# OST.net
KiCad netlist of a schematic drawn in EAGLE
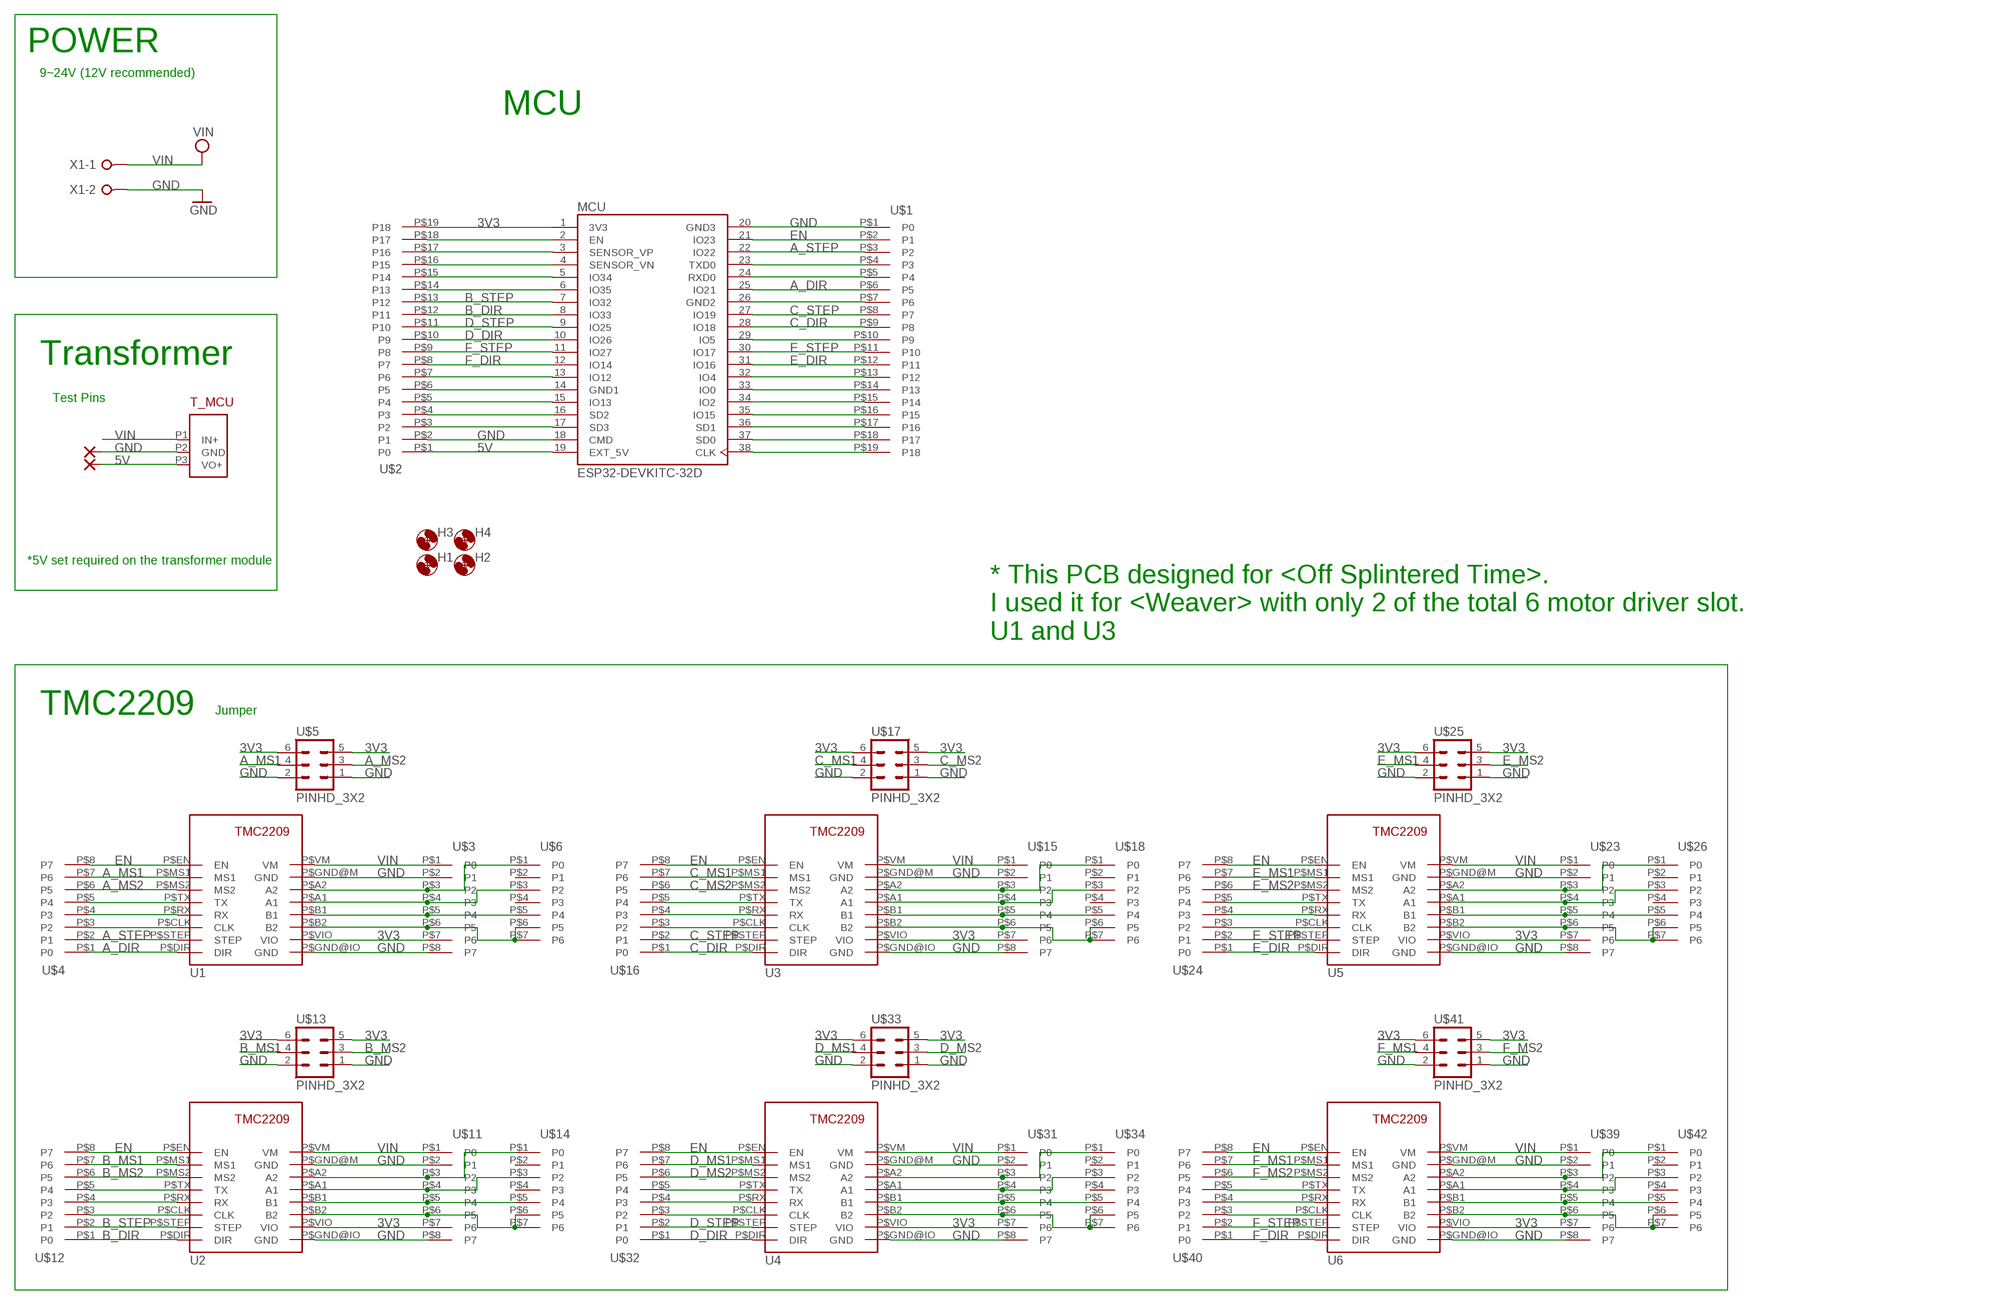
[diagram p0: schematic, sheet 1]

(export (version "E")
  (design (tool "Eeschema 10.0.6"))
  (components
    (comp (ref "H1")
      (value "MOUNT-HOLE3.2")
      (footprint "eagle-import:3,2")
      (libsource (lib "eagle-import") (part "MOUNT-HOLE3.2"))
    )
    (comp (ref "H2")
      (value "MOUNT-HOLE3.2")
      (footprint "eagle-import:3,2")
      (libsource (lib "eagle-import") (part "MOUNT-HOLE3.2"))
    )
    (comp (ref "H3")
      (value "MOUNT-HOLE3.2")
      (footprint "eagle-import:3,2")
      (libsource (lib "eagle-import") (part "MOUNT-HOLE3.2"))
    )
    (comp (ref "H4")
      (value "MOUNT-HOLE3.2")
      (footprint "eagle-import:3,2")
      (libsource (lib "eagle-import") (part "MOUNT-HOLE3.2"))
    )
    (comp (ref "MCU")
      (value "ESP32-DEVKITC-32D")
      (footprint "eagle-import:MODULE_ESP32-DEVKITC-32D")
      (fields (field (name "MANUFACTURER") "Espressif Systems"))
      (libsource (lib "eagle-import") (part "ESP32-DEVKITC-32D"))
    )
    (comp (ref "PAD16")
      (value "2,15/1,0")
      (footprint "eagle-import:2,15_1,0")
      (libsource (lib "eagle-import") (part "2,15/1,0"))
    )
    (comp (ref "PAD17")
      (value "2,15/1,0")
      (footprint "eagle-import:2,15_1,0")
      (libsource (lib "eagle-import") (part "2,15/1,0"))
    )
    (comp (ref "T_MCU")
      (value "VOL_ADJ")
      (footprint "eagle-import:FREEVOL")
      (libsource (lib "eagle-import") (part "VOL_ADJ"))
    )
    (comp (ref "U$1")
      (value "PINHD_1X19")
      (footprint "eagle-import:19")
      (libsource (lib "eagle-import") (part "PINHD_1X19"))
    )
    (comp (ref "U$2")
      (value "PINHD_1X19")
      (footprint "eagle-import:19")
      (libsource (lib "eagle-import") (part "PINHD_1X19"))
    )
    (comp (ref "U$3")
      (value "PINHD_1X8")
      (footprint "eagle-import:8")
      (libsource (lib "eagle-import") (part "PINHD_1X8"))
    )
    (comp (ref "U$4")
      (value "PINHD_1X8")
      (footprint "eagle-import:8")
      (libsource (lib "eagle-import") (part "PINHD_1X8"))
    )
    (comp (ref "U$5")
      (value "PINHD_3X2")
      (footprint "eagle-import:MA03-2")
      (libsource (lib "eagle-import") (part "PINHD_3X2"))
    )
    (comp (ref "U$6")
      (value "PINHD_1X7")
      (footprint "eagle-import:7")
      (libsource (lib "eagle-import") (part "PINHD_1X7"))
    )
    (comp (ref "U$11")
      (value "PINHD_1X8")
      (footprint "eagle-import:8")
      (libsource (lib "eagle-import") (part "PINHD_1X8"))
    )
    (comp (ref "U$12")
      (value "PINHD_1X8")
      (footprint "eagle-import:8")
      (libsource (lib "eagle-import") (part "PINHD_1X8"))
    )
    (comp (ref "U$13")
      (value "PINHD_3X2")
      (footprint "eagle-import:MA03-2")
      (libsource (lib "eagle-import") (part "PINHD_3X2"))
    )
    (comp (ref "U$14")
      (value "PINHD_1X7")
      (footprint "eagle-import:7")
      (libsource (lib "eagle-import") (part "PINHD_1X7"))
    )
    (comp (ref "U$15")
      (value "PINHD_1X8")
      (footprint "eagle-import:8")
      (libsource (lib "eagle-import") (part "PINHD_1X8"))
    )
    (comp (ref "U$16")
      (value "PINHD_1X8")
      (footprint "eagle-import:8")
      (libsource (lib "eagle-import") (part "PINHD_1X8"))
    )
    (comp (ref "U$17")
      (value "PINHD_3X2")
      (footprint "eagle-import:MA03-2")
      (libsource (lib "eagle-import") (part "PINHD_3X2"))
    )
    (comp (ref "U$18")
      (value "PINHD_1X7")
      (footprint "eagle-import:7")
      (libsource (lib "eagle-import") (part "PINHD_1X7"))
    )
    (comp (ref "U$23")
      (value "PINHD_1X8")
      (footprint "eagle-import:8")
      (libsource (lib "eagle-import") (part "PINHD_1X8"))
    )
    (comp (ref "U$24")
      (value "PINHD_1X8")
      (footprint "eagle-import:8")
      (libsource (lib "eagle-import") (part "PINHD_1X8"))
    )
    (comp (ref "U$25")
      (value "PINHD_3X2")
      (footprint "eagle-import:MA03-2")
      (libsource (lib "eagle-import") (part "PINHD_3X2"))
    )
    (comp (ref "U$26")
      (value "PINHD_1X7")
      (footprint "eagle-import:7")
      (libsource (lib "eagle-import") (part "PINHD_1X7"))
    )
    (comp (ref "U$31")
      (value "PINHD_1X8")
      (footprint "eagle-import:8")
      (libsource (lib "eagle-import") (part "PINHD_1X8"))
    )
    (comp (ref "U$32")
      (value "PINHD_1X8")
      (footprint "eagle-import:8")
      (libsource (lib "eagle-import") (part "PINHD_1X8"))
    )
    (comp (ref "U$33")
      (value "PINHD_3X2")
      (footprint "eagle-import:MA03-2")
      (libsource (lib "eagle-import") (part "PINHD_3X2"))
    )
    (comp (ref "U$34")
      (value "PINHD_1X7")
      (footprint "eagle-import:7")
      (libsource (lib "eagle-import") (part "PINHD_1X7"))
    )
    (comp (ref "U$39")
      (value "PINHD_1X8")
      (footprint "eagle-import:8")
      (libsource (lib "eagle-import") (part "PINHD_1X8"))
    )
    (comp (ref "U$40")
      (value "PINHD_1X8")
      (footprint "eagle-import:8")
      (libsource (lib "eagle-import") (part "PINHD_1X8"))
    )
    (comp (ref "U$41")
      (value "PINHD_3X2")
      (footprint "eagle-import:MA03-2")
      (libsource (lib "eagle-import") (part "PINHD_3X2"))
    )
    (comp (ref "U$42")
      (value "PINHD_1X7")
      (footprint "eagle-import:7")
      (libsource (lib "eagle-import") (part "PINHD_1X7"))
    )
    (comp (ref "U1")
      (value "TMC2209_V3.1")
      (footprint "eagle-import:TMC2209")
      (libsource (lib "eagle-import") (part "TMC2209_V3.1"))
    )
    (comp (ref "U2")
      (value "TMC2209_V3.1")
      (footprint "eagle-import:TMC2209")
      (libsource (lib "eagle-import") (part "TMC2209_V3.1"))
    )
    (comp (ref "U3")
      (value "TMC2209_V3.1")
      (footprint "eagle-import:TMC2209")
      (libsource (lib "eagle-import") (part "TMC2209_V3.1"))
    )
    (comp (ref "U4")
      (value "TMC2209_V3.1")
      (footprint "eagle-import:TMC2209")
      (libsource (lib "eagle-import") (part "TMC2209_V3.1"))
    )
    (comp (ref "U5")
      (value "TMC2209_V3.1")
      (footprint "eagle-import:TMC2209")
      (libsource (lib "eagle-import") (part "TMC2209_V3.1"))
    )
    (comp (ref "U6")
      (value "TMC2209_V3.1")
      (footprint "eagle-import:TMC2209")
      (libsource (lib "eagle-import") (part "TMC2209_V3.1"))
    )
    (comp (ref "X1")
      (value "W237-02P")
      (footprint "eagle-import:W237-132")
      (libsource (lib "eagle-import") (part "W237-02P"))
    )
  )
  (nets
    (net (code "1") (name "/3V3") (class "Default")
      (node (ref "MCU") (pin "1") (pinfunction "3V3_1") (pintype "power_in"))
      (node (ref "U$11") (pin "P$7") (pinfunction "P6_P$7") (pintype "bidirectional"))
      (node (ref "U$13") (pin "5") (pinfunction "5_5") (pintype "passive"))
      (node (ref "U$13") (pin "6") (pinfunction "6_6") (pintype "passive"))
      (node (ref "U$15") (pin "P$7") (pinfunction "P6_P$7") (pintype "bidirectional"))
      (node (ref "U$17") (pin "5") (pinfunction "5_5") (pintype "passive"))
      (node (ref "U$17") (pin "6") (pinfunction "6_6") (pintype "passive"))
      (node (ref "U$2") (pin "P$19") (pinfunction "P18_P$19") (pintype "bidirectional"))
      (node (ref "U$23") (pin "P$7") (pinfunction "P6_P$7") (pintype "bidirectional"))
      (node (ref "U$25") (pin "5") (pinfunction "5_5") (pintype "passive"))
      (node (ref "U$25") (pin "6") (pinfunction "6_6") (pintype "passive"))
      (node (ref "U$3") (pin "P$7") (pinfunction "P6_P$7") (pintype "bidirectional"))
      (node (ref "U$31") (pin "P$7") (pinfunction "P6_P$7") (pintype "bidirectional"))
      (node (ref "U$33") (pin "5") (pinfunction "5_5") (pintype "passive"))
      (node (ref "U$33") (pin "6") (pinfunction "6_6") (pintype "passive"))
      (node (ref "U$39") (pin "P$7") (pinfunction "P6_P$7") (pintype "bidirectional"))
      (node (ref "U$41") (pin "5") (pinfunction "5_5") (pintype "passive"))
      (node (ref "U$41") (pin "6") (pinfunction "6_6") (pintype "passive"))
      (node (ref "U$5") (pin "5") (pinfunction "5_5") (pintype "passive"))
      (node (ref "U$5") (pin "6") (pinfunction "6_6") (pintype "passive"))
      (node (ref "U1") (pin "P$VIO") (pinfunction "VIO_P$VIO") (pintype "bidirectional"))
      (node (ref "U2") (pin "P$VIO") (pinfunction "VIO_P$VIO") (pintype "bidirectional"))
      (node (ref "U3") (pin "P$VIO") (pinfunction "VIO_P$VIO") (pintype "bidirectional"))
      (node (ref "U4") (pin "P$VIO") (pinfunction "VIO_P$VIO") (pintype "bidirectional"))
      (node (ref "U5") (pin "P$VIO") (pinfunction "VIO_P$VIO") (pintype "bidirectional"))
      (node (ref "U6") (pin "P$VIO") (pinfunction "VIO_P$VIO") (pintype "bidirectional"))
    )
    (net (code "2") (name "/5V") (class "Default")
      (node (ref "MCU") (pin "19") (pinfunction "EXT_5V_19") (pintype "power_in"))
      (node (ref "PAD17") (pin "1") (pinfunction "P_1") (pintype "passive"))
      (node (ref "T_MCU") (pin "P3") (pinfunction "VO+_P3") (pintype "bidirectional"))
      (node (ref "U$2") (pin "P$1") (pinfunction "P0_P$1") (pintype "bidirectional"))
    )
    (net (code "3") (name "/A_DIR") (class "Default")
      (node (ref "MCU") (pin "25") (pinfunction "IO21_25") (pintype "bidirectional"))
      (node (ref "U$1") (pin "P$6") (pinfunction "P5_P$6") (pintype "bidirectional"))
      (node (ref "U$4") (pin "P$1") (pinfunction "P0_P$1") (pintype "bidirectional"))
      (node (ref "U1") (pin "P$DIR") (pinfunction "DIR_P$DIR") (pintype "bidirectional"))
    )
    (net (code "4") (name "/A_MS1") (class "Default")
      (node (ref "U$4") (pin "P$7") (pinfunction "P6_P$7") (pintype "bidirectional"))
      (node (ref "U$5") (pin "4") (pinfunction "4_4") (pintype "passive"))
      (node (ref "U1") (pin "P$MS1") (pinfunction "MS1_P$MS1") (pintype "bidirectional"))
    )
    (net (code "5") (name "/A_MS2") (class "Default")
      (node (ref "U$4") (pin "P$6") (pinfunction "P5_P$6") (pintype "bidirectional"))
      (node (ref "U$5") (pin "3") (pinfunction "3_3") (pintype "passive"))
      (node (ref "U1") (pin "P$MS2") (pinfunction "MS2_P$MS2") (pintype "bidirectional"))
    )
    (net (code "6") (name "/A_STEP") (class "Default")
      (node (ref "MCU") (pin "22") (pinfunction "IO22_22") (pintype "bidirectional"))
      (node (ref "U$1") (pin "P$3") (pinfunction "P2_P$3") (pintype "bidirectional"))
      (node (ref "U$4") (pin "P$2") (pinfunction "P1_P$2") (pintype "bidirectional"))
      (node (ref "U1") (pin "P$STEP") (pinfunction "STEP_P$STEP") (pintype "bidirectional"))
    )
    (net (code "7") (name "/B_DIR") (class "Default")
      (node (ref "MCU") (pin "8") (pinfunction "IO33_8") (pintype "bidirectional"))
      (node (ref "U$12") (pin "P$1") (pinfunction "P0_P$1") (pintype "bidirectional"))
      (node (ref "U$2") (pin "P$12") (pinfunction "P11_P$12") (pintype "bidirectional"))
      (node (ref "U2") (pin "P$DIR") (pinfunction "DIR_P$DIR") (pintype "bidirectional"))
    )
    (net (code "8") (name "/B_MS1") (class "Default")
      (node (ref "U$12") (pin "P$7") (pinfunction "P6_P$7") (pintype "bidirectional"))
      (node (ref "U$13") (pin "4") (pinfunction "4_4") (pintype "passive"))
      (node (ref "U2") (pin "P$MS1") (pinfunction "MS1_P$MS1") (pintype "bidirectional"))
    )
    (net (code "9") (name "/B_MS2") (class "Default")
      (node (ref "U$12") (pin "P$6") (pinfunction "P5_P$6") (pintype "bidirectional"))
      (node (ref "U$13") (pin "3") (pinfunction "3_3") (pintype "passive"))
      (node (ref "U2") (pin "P$MS2") (pinfunction "MS2_P$MS2") (pintype "bidirectional"))
    )
    (net (code "10") (name "/B_STEP") (class "Default")
      (node (ref "MCU") (pin "7") (pinfunction "IO32_7") (pintype "bidirectional"))
      (node (ref "U$12") (pin "P$2") (pinfunction "P1_P$2") (pintype "bidirectional"))
      (node (ref "U$2") (pin "P$13") (pinfunction "P12_P$13") (pintype "bidirectional"))
      (node (ref "U2") (pin "P$STEP") (pinfunction "STEP_P$STEP") (pintype "bidirectional"))
    )
    (net (code "11") (name "/C_DIR") (class "Default")
      (node (ref "MCU") (pin "28") (pinfunction "IO18_28") (pintype "bidirectional"))
      (node (ref "U$1") (pin "P$9") (pinfunction "P8_P$9") (pintype "bidirectional"))
      (node (ref "U$16") (pin "P$1") (pinfunction "P0_P$1") (pintype "bidirectional"))
      (node (ref "U3") (pin "P$DIR") (pinfunction "DIR_P$DIR") (pintype "bidirectional"))
    )
    (net (code "12") (name "/C_MS1") (class "Default")
      (node (ref "U$16") (pin "P$7") (pinfunction "P6_P$7") (pintype "bidirectional"))
      (node (ref "U$17") (pin "4") (pinfunction "4_4") (pintype "passive"))
      (node (ref "U3") (pin "P$MS1") (pinfunction "MS1_P$MS1") (pintype "bidirectional"))
    )
    (net (code "13") (name "/C_MS2") (class "Default")
      (node (ref "U$16") (pin "P$6") (pinfunction "P5_P$6") (pintype "bidirectional"))
      (node (ref "U$17") (pin "3") (pinfunction "3_3") (pintype "passive"))
      (node (ref "U3") (pin "P$MS2") (pinfunction "MS2_P$MS2") (pintype "bidirectional"))
    )
    (net (code "14") (name "/C_STEP") (class "Default")
      (node (ref "MCU") (pin "27") (pinfunction "IO19_27") (pintype "bidirectional"))
      (node (ref "U$1") (pin "P$8") (pinfunction "P7_P$8") (pintype "bidirectional"))
      (node (ref "U$16") (pin "P$2") (pinfunction "P1_P$2") (pintype "bidirectional"))
      (node (ref "U3") (pin "P$STEP") (pinfunction "STEP_P$STEP") (pintype "bidirectional"))
    )
    (net (code "15") (name "/D_DIR") (class "Default")
      (node (ref "MCU") (pin "10") (pinfunction "IO26_10") (pintype "bidirectional"))
      (node (ref "U$2") (pin "P$10") (pinfunction "P9_P$10") (pintype "bidirectional"))
      (node (ref "U$32") (pin "P$1") (pinfunction "P0_P$1") (pintype "bidirectional"))
      (node (ref "U4") (pin "P$DIR") (pinfunction "DIR_P$DIR") (pintype "bidirectional"))
    )
    (net (code "16") (name "/D_MS1") (class "Default")
      (node (ref "U$32") (pin "P$7") (pinfunction "P6_P$7") (pintype "bidirectional"))
      (node (ref "U$33") (pin "4") (pinfunction "4_4") (pintype "passive"))
      (node (ref "U4") (pin "P$MS1") (pinfunction "MS1_P$MS1") (pintype "bidirectional"))
    )
    (net (code "17") (name "/D_MS2") (class "Default")
      (node (ref "U$32") (pin "P$6") (pinfunction "P5_P$6") (pintype "bidirectional"))
      (node (ref "U$33") (pin "3") (pinfunction "3_3") (pintype "passive"))
      (node (ref "U4") (pin "P$MS2") (pinfunction "MS2_P$MS2") (pintype "bidirectional"))
    )
    (net (code "18") (name "/D_STEP") (class "Default")
      (node (ref "MCU") (pin "9") (pinfunction "IO25_9") (pintype "bidirectional"))
      (node (ref "U$2") (pin "P$11") (pinfunction "P10_P$11") (pintype "bidirectional"))
      (node (ref "U$32") (pin "P$2") (pinfunction "P1_P$2") (pintype "bidirectional"))
      (node (ref "U4") (pin "P$STEP") (pinfunction "STEP_P$STEP") (pintype "bidirectional"))
    )
    (net (code "19") (name "/EN") (class "Default")
      (node (ref "MCU") (pin "21") (pinfunction "IO23_21") (pintype "bidirectional"))
      (node (ref "U$1") (pin "P$2") (pinfunction "P1_P$2") (pintype "bidirectional"))
      (node (ref "U$12") (pin "P$8") (pinfunction "P7_P$8") (pintype "bidirectional"))
      (node (ref "U$16") (pin "P$8") (pinfunction "P7_P$8") (pintype "bidirectional"))
      (node (ref "U$24") (pin "P$8") (pinfunction "P7_P$8") (pintype "bidirectional"))
      (node (ref "U$32") (pin "P$8") (pinfunction "P7_P$8") (pintype "bidirectional"))
      (node (ref "U$4") (pin "P$8") (pinfunction "P7_P$8") (pintype "bidirectional"))
      (node (ref "U$40") (pin "P$8") (pinfunction "P7_P$8") (pintype "bidirectional"))
      (node (ref "U1") (pin "P$EN") (pinfunction "EN_P$EN") (pintype "bidirectional"))
      (node (ref "U2") (pin "P$EN") (pinfunction "EN_P$EN") (pintype "bidirectional"))
      (node (ref "U3") (pin "P$EN") (pinfunction "EN_P$EN") (pintype "bidirectional"))
      (node (ref "U4") (pin "P$EN") (pinfunction "EN_P$EN") (pintype "bidirectional"))
      (node (ref "U5") (pin "P$EN") (pinfunction "EN_P$EN") (pintype "bidirectional"))
      (node (ref "U6") (pin "P$EN") (pinfunction "EN_P$EN") (pintype "bidirectional"))
    )
    (net (code "20") (name "/E_DIR") (class "Default")
      (node (ref "MCU") (pin "31") (pinfunction "IO16_31") (pintype "bidirectional"))
      (node (ref "U$1") (pin "P$12") (pinfunction "P11_P$12") (pintype "bidirectional"))
      (node (ref "U$24") (pin "P$1") (pinfunction "P0_P$1") (pintype "bidirectional"))
      (node (ref "U5") (pin "P$DIR") (pinfunction "DIR_P$DIR") (pintype "bidirectional"))
    )
    (net (code "21") (name "/E_MS1") (class "Default")
      (node (ref "U$24") (pin "P$7") (pinfunction "P6_P$7") (pintype "bidirectional"))
      (node (ref "U$25") (pin "4") (pinfunction "4_4") (pintype "passive"))
      (node (ref "U5") (pin "P$MS1") (pinfunction "MS1_P$MS1") (pintype "bidirectional"))
    )
    (net (code "22") (name "/E_MS2") (class "Default")
      (node (ref "U$24") (pin "P$6") (pinfunction "P5_P$6") (pintype "bidirectional"))
      (node (ref "U$25") (pin "3") (pinfunction "3_3") (pintype "passive"))
      (node (ref "U5") (pin "P$MS2") (pinfunction "MS2_P$MS2") (pintype "bidirectional"))
    )
    (net (code "23") (name "/E_STEP") (class "Default")
      (node (ref "MCU") (pin "30") (pinfunction "IO17_30") (pintype "bidirectional"))
      (node (ref "U$1") (pin "P$11") (pinfunction "P10_P$11") (pintype "bidirectional"))
      (node (ref "U$24") (pin "P$2") (pinfunction "P1_P$2") (pintype "bidirectional"))
      (node (ref "U5") (pin "P$STEP") (pinfunction "STEP_P$STEP") (pintype "bidirectional"))
    )
    (net (code "24") (name "/F_DIR") (class "Default")
      (node (ref "MCU") (pin "12") (pinfunction "IO14_12") (pintype "bidirectional"))
      (node (ref "U$2") (pin "P$8") (pinfunction "P7_P$8") (pintype "bidirectional"))
      (node (ref "U$40") (pin "P$1") (pinfunction "P0_P$1") (pintype "bidirectional"))
      (node (ref "U6") (pin "P$DIR") (pinfunction "DIR_P$DIR") (pintype "bidirectional"))
    )
    (net (code "25") (name "/F_MS1") (class "Default")
      (node (ref "U$40") (pin "P$7") (pinfunction "P6_P$7") (pintype "bidirectional"))
      (node (ref "U$41") (pin "4") (pinfunction "4_4") (pintype "passive"))
      (node (ref "U6") (pin "P$MS1") (pinfunction "MS1_P$MS1") (pintype "bidirectional"))
    )
    (net (code "26") (name "/F_MS2") (class "Default")
      (node (ref "U$40") (pin "P$6") (pinfunction "P5_P$6") (pintype "bidirectional"))
      (node (ref "U$41") (pin "3") (pinfunction "3_3") (pintype "passive"))
      (node (ref "U6") (pin "P$MS2") (pinfunction "MS2_P$MS2") (pintype "bidirectional"))
    )
    (net (code "27") (name "/F_STEP") (class "Default")
      (node (ref "MCU") (pin "11") (pinfunction "IO27_11") (pintype "bidirectional"))
      (node (ref "U$2") (pin "P$9") (pinfunction "P8_P$9") (pintype "bidirectional"))
      (node (ref "U$40") (pin "P$2") (pinfunction "P1_P$2") (pintype "bidirectional"))
      (node (ref "U6") (pin "P$STEP") (pinfunction "STEP_P$STEP") (pintype "bidirectional"))
    )
    (net (code "28") (name "GND") (class "Default")
      (node (ref "MCU") (pin "18") (pinfunction "CMD_18") (pintype "bidirectional"))
      (node (ref "MCU") (pin "20") (pinfunction "GND3_20") (pintype "power_in"))
      (node (ref "PAD16") (pin "1") (pinfunction "P_1") (pintype "passive"))
      (node (ref "T_MCU") (pin "P2") (pinfunction "GND_P2") (pintype "bidirectional"))
      (node (ref "U$1") (pin "P$1") (pinfunction "P0_P$1") (pintype "bidirectional"))
      (node (ref "U$11") (pin "P$2") (pinfunction "P1_P$2") (pintype "bidirectional"))
      (node (ref "U$11") (pin "P$8") (pinfunction "P7_P$8") (pintype "bidirectional"))
      (node (ref "U$13") (pin "1") (pinfunction "1_1") (pintype "passive"))
      (node (ref "U$13") (pin "2") (pinfunction "2_2") (pintype "passive"))
      (node (ref "U$15") (pin "P$2") (pinfunction "P1_P$2") (pintype "bidirectional"))
      (node (ref "U$15") (pin "P$8") (pinfunction "P7_P$8") (pintype "bidirectional"))
      (node (ref "U$17") (pin "1") (pinfunction "1_1") (pintype "passive"))
      (node (ref "U$17") (pin "2") (pinfunction "2_2") (pintype "passive"))
      (node (ref "U$2") (pin "P$2") (pinfunction "P1_P$2") (pintype "bidirectional"))
      (node (ref "U$23") (pin "P$2") (pinfunction "P1_P$2") (pintype "bidirectional"))
      (node (ref "U$23") (pin "P$8") (pinfunction "P7_P$8") (pintype "bidirectional"))
      (node (ref "U$25") (pin "1") (pinfunction "1_1") (pintype "passive"))
      (node (ref "U$25") (pin "2") (pinfunction "2_2") (pintype "passive"))
      (node (ref "U$3") (pin "P$2") (pinfunction "P1_P$2") (pintype "bidirectional"))
      (node (ref "U$3") (pin "P$8") (pinfunction "P7_P$8") (pintype "bidirectional"))
      (node (ref "U$31") (pin "P$2") (pinfunction "P1_P$2") (pintype "bidirectional"))
      (node (ref "U$31") (pin "P$8") (pinfunction "P7_P$8") (pintype "bidirectional"))
      (node (ref "U$33") (pin "1") (pinfunction "1_1") (pintype "passive"))
      (node (ref "U$33") (pin "2") (pinfunction "2_2") (pintype "passive"))
      (node (ref "U$39") (pin "P$2") (pinfunction "P1_P$2") (pintype "bidirectional"))
      (node (ref "U$39") (pin "P$8") (pinfunction "P7_P$8") (pintype "bidirectional"))
      (node (ref "U$41") (pin "1") (pinfunction "1_1") (pintype "passive"))
      (node (ref "U$41") (pin "2") (pinfunction "2_2") (pintype "passive"))
      (node (ref "U$5") (pin "1") (pinfunction "1_1") (pintype "passive"))
      (node (ref "U$5") (pin "2") (pinfunction "2_2") (pintype "passive"))
      (node (ref "U1") (pin "P$GND@IO") (pinfunction "GND_P$GND@IO") (pintype "bidirectional"))
      (node (ref "U1") (pin "P$GND@M") (pinfunction "GND_P$GND@M") (pintype "bidirectional"))
      (node (ref "U2") (pin "P$GND@IO") (pinfunction "GND_P$GND@IO") (pintype "bidirectional"))
      (node (ref "U2") (pin "P$GND@M") (pinfunction "GND_P$GND@M") (pintype "bidirectional"))
      (node (ref "U3") (pin "P$GND@IO") (pinfunction "GND_P$GND@IO") (pintype "bidirectional"))
      (node (ref "U3") (pin "P$GND@M") (pinfunction "GND_P$GND@M") (pintype "bidirectional"))
      (node (ref "U4") (pin "P$GND@IO") (pinfunction "GND_P$GND@IO") (pintype "bidirectional"))
      (node (ref "U4") (pin "P$GND@M") (pinfunction "GND_P$GND@M") (pintype "bidirectional"))
      (node (ref "U5") (pin "P$GND@IO") (pinfunction "GND_P$GND@IO") (pintype "bidirectional"))
      (node (ref "U5") (pin "P$GND@M") (pinfunction "GND_P$GND@M") (pintype "bidirectional"))
      (node (ref "U6") (pin "P$GND@IO") (pinfunction "GND_P$GND@IO") (pintype "bidirectional"))
      (node (ref "U6") (pin "P$GND@M") (pinfunction "GND_P$GND@M") (pintype "bidirectional"))
      (node (ref "X1") (pin "2") (pinfunction "KL_2") (pintype "passive"))
    )
    (net (code "29") (name "Net-(MCU-CLK)") (class "Default")
      (node (ref "MCU") (pin "38") (pinfunction "CLK_38") (pintype "input"))
      (node (ref "U$1") (pin "P$19") (pinfunction "P18_P$19") (pintype "bidirectional"))
    )
    (net (code "30") (name "Net-(MCU-EN)") (class "Default")
      (node (ref "MCU") (pin "2") (pinfunction "EN_2") (pintype "input"))
      (node (ref "U$2") (pin "P$18") (pinfunction "P17_P$18") (pintype "bidirectional"))
    )
    (net (code "31") (name "Net-(MCU-GND1)") (class "Default")
      (node (ref "MCU") (pin "14") (pinfunction "GND1_14") (pintype "power_in"))
      (node (ref "U$2") (pin "P$6") (pinfunction "P5_P$6") (pintype "bidirectional"))
    )
    (net (code "32") (name "Net-(MCU-GND2)") (class "Default")
      (node (ref "MCU") (pin "26") (pinfunction "GND2_26") (pintype "power_in"))
      (node (ref "U$1") (pin "P$7") (pinfunction "P6_P$7") (pintype "bidirectional"))
    )
    (net (code "33") (name "Net-(MCU-IO0)") (class "Default")
      (node (ref "MCU") (pin "33") (pinfunction "IO0_33") (pintype "bidirectional"))
      (node (ref "U$1") (pin "P$14") (pinfunction "P13_P$14") (pintype "bidirectional"))
    )
    (net (code "34") (name "Net-(MCU-IO2)") (class "Default")
      (node (ref "MCU") (pin "34") (pinfunction "IO2_34") (pintype "bidirectional"))
      (node (ref "U$1") (pin "P$15") (pinfunction "P14_P$15") (pintype "bidirectional"))
    )
    (net (code "35") (name "Net-(MCU-IO4)") (class "Default")
      (node (ref "MCU") (pin "32") (pinfunction "IO4_32") (pintype "bidirectional"))
      (node (ref "U$1") (pin "P$13") (pinfunction "P12_P$13") (pintype "bidirectional"))
    )
    (net (code "36") (name "Net-(MCU-IO5)") (class "Default")
      (node (ref "MCU") (pin "29") (pinfunction "IO5_29") (pintype "bidirectional"))
      (node (ref "U$1") (pin "P$10") (pinfunction "P9_P$10") (pintype "bidirectional"))
    )
    (net (code "37") (name "Net-(MCU-IO12)") (class "Default")
      (node (ref "MCU") (pin "13") (pinfunction "IO12_13") (pintype "bidirectional"))
      (node (ref "U$2") (pin "P$7") (pinfunction "P6_P$7") (pintype "bidirectional"))
    )
    (net (code "38") (name "Net-(MCU-IO13)") (class "Default")
      (node (ref "MCU") (pin "15") (pinfunction "IO13_15") (pintype "bidirectional"))
      (node (ref "U$2") (pin "P$5") (pinfunction "P4_P$5") (pintype "bidirectional"))
    )
    (net (code "39") (name "Net-(MCU-IO15)") (class "Default")
      (node (ref "MCU") (pin "35") (pinfunction "IO15_35") (pintype "bidirectional"))
      (node (ref "U$1") (pin "P$16") (pinfunction "P15_P$16") (pintype "bidirectional"))
    )
    (net (code "40") (name "Net-(MCU-IO34)") (class "Default")
      (node (ref "MCU") (pin "5") (pinfunction "IO34_5") (pintype "bidirectional"))
      (node (ref "U$2") (pin "P$15") (pinfunction "P14_P$15") (pintype "bidirectional"))
    )
    (net (code "41") (name "Net-(MCU-IO35)") (class "Default")
      (node (ref "MCU") (pin "6") (pinfunction "IO35_6") (pintype "bidirectional"))
      (node (ref "U$2") (pin "P$14") (pinfunction "P13_P$14") (pintype "bidirectional"))
    )
    (net (code "42") (name "Net-(MCU-RXD0)") (class "Default")
      (node (ref "MCU") (pin "24") (pinfunction "RXD0_24") (pintype "input"))
      (node (ref "U$1") (pin "P$5") (pinfunction "P4_P$5") (pintype "bidirectional"))
    )
    (net (code "43") (name "Net-(MCU-SD0)") (class "Default")
      (node (ref "MCU") (pin "37") (pinfunction "SD0_37") (pintype "bidirectional"))
      (node (ref "U$1") (pin "P$18") (pinfunction "P17_P$18") (pintype "bidirectional"))
    )
    (net (code "44") (name "Net-(MCU-SD1)") (class "Default")
      (node (ref "MCU") (pin "36") (pinfunction "SD1_36") (pintype "bidirectional"))
      (node (ref "U$1") (pin "P$17") (pinfunction "P16_P$17") (pintype "bidirectional"))
    )
    (net (code "45") (name "Net-(MCU-SD2)") (class "Default")
      (node (ref "MCU") (pin "16") (pinfunction "SD2_16") (pintype "bidirectional"))
      (node (ref "U$2") (pin "P$4") (pinfunction "P3_P$4") (pintype "bidirectional"))
    )
    (net (code "46") (name "Net-(MCU-SD3)") (class "Default")
      (node (ref "MCU") (pin "17") (pinfunction "SD3_17") (pintype "bidirectional"))
      (node (ref "U$2") (pin "P$3") (pinfunction "P2_P$3") (pintype "bidirectional"))
    )
    (net (code "47") (name "Net-(MCU-SENSOR_VN)") (class "Default")
      (node (ref "MCU") (pin "4") (pinfunction "SENSOR_VN_4") (pintype "input"))
      (node (ref "U$2") (pin "P$16") (pinfunction "P15_P$16") (pintype "bidirectional"))
    )
    (net (code "48") (name "Net-(MCU-SENSOR_VP)") (class "Default")
      (node (ref "MCU") (pin "3") (pinfunction "SENSOR_VP_3") (pintype "input"))
      (node (ref "U$2") (pin "P$17") (pinfunction "P16_P$17") (pintype "bidirectional"))
    )
    (net (code "49") (name "Net-(MCU-TXD0)") (class "Default")
      (node (ref "MCU") (pin "23") (pinfunction "TXD0_23") (pintype "output"))
      (node (ref "U$1") (pin "P$4") (pinfunction "P3_P$4") (pintype "bidirectional"))
    )
    (net (code "50") (name "Net-(U$3-P2)") (class "Default")
      (node (ref "U$3") (pin "P$3") (pinfunction "P2_P$3") (pintype "bidirectional"))
      (node (ref "U$6") (pin "P$1") (pinfunction "P0_P$1") (pintype "bidirectional"))
      (node (ref "U1") (pin "P$A2") (pinfunction "A2_P$A2") (pintype "bidirectional"))
    )
    (net (code "51") (name "Net-(U$3-P3)") (class "Default")
      (node (ref "U$3") (pin "P$4") (pinfunction "P3_P$4") (pintype "bidirectional"))
      (node (ref "U$6") (pin "P$3") (pinfunction "P2_P$3") (pintype "bidirectional"))
      (node (ref "U1") (pin "P$A1") (pinfunction "A1_P$A1") (pintype "bidirectional"))
    )
    (net (code "52") (name "Net-(U$3-P4)") (class "Default")
      (node (ref "U$3") (pin "P$5") (pinfunction "P4_P$5") (pintype "bidirectional"))
      (node (ref "U$6") (pin "P$5") (pinfunction "P4_P$5") (pintype "bidirectional"))
      (node (ref "U1") (pin "P$B1") (pinfunction "B1_P$B1") (pintype "bidirectional"))
    )
    (net (code "53") (name "Net-(U$3-P5)") (class "Default")
      (node (ref "U$3") (pin "P$6") (pinfunction "P5_P$6") (pintype "bidirectional"))
      (node (ref "U$6") (pin "P$6") (pinfunction "P5_P$6") (pintype "bidirectional"))
      (node (ref "U$6") (pin "P$7") (pinfunction "P6_P$7") (pintype "bidirectional"))
      (node (ref "U1") (pin "P$B2") (pinfunction "B2_P$B2") (pintype "bidirectional"))
    )
    (net (code "54") (name "Net-(U$4-P2)") (class "Default")
      (node (ref "U$4") (pin "P$3") (pinfunction "P2_P$3") (pintype "bidirectional"))
      (node (ref "U1") (pin "P$CLK") (pinfunction "CLK_P$CLK") (pintype "bidirectional"))
    )
    (net (code "55") (name "Net-(U$4-P3)") (class "Default")
      (node (ref "U$4") (pin "P$4") (pinfunction "P3_P$4") (pintype "bidirectional"))
      (node (ref "U1") (pin "P$RX") (pinfunction "RX_P$RX") (pintype "bidirectional"))
    )
    (net (code "56") (name "Net-(U$4-P4)") (class "Default")
      (node (ref "U$4") (pin "P$5") (pinfunction "P4_P$5") (pintype "bidirectional"))
      (node (ref "U1") (pin "P$TX") (pinfunction "TX_P$TX") (pintype "bidirectional"))
    )
    (net (code "57") (name "Net-(U$11-P2)") (class "Default")
      (node (ref "U$11") (pin "P$3") (pinfunction "P2_P$3") (pintype "bidirectional"))
      (node (ref "U$14") (pin "P$1") (pinfunction "P0_P$1") (pintype "bidirectional"))
      (node (ref "U2") (pin "P$A2") (pinfunction "A2_P$A2") (pintype "bidirectional"))
    )
    (net (code "58") (name "Net-(U$11-P3)") (class "Default")
      (node (ref "U$11") (pin "P$4") (pinfunction "P3_P$4") (pintype "bidirectional"))
      (node (ref "U$14") (pin "P$3") (pinfunction "P2_P$3") (pintype "bidirectional"))
      (node (ref "U2") (pin "P$A1") (pinfunction "A1_P$A1") (pintype "bidirectional"))
    )
    (net (code "59") (name "Net-(U$11-P4)") (class "Default")
      (node (ref "U$11") (pin "P$5") (pinfunction "P4_P$5") (pintype "bidirectional"))
      (node (ref "U$14") (pin "P$5") (pinfunction "P4_P$5") (pintype "bidirectional"))
      (node (ref "U2") (pin "P$B1") (pinfunction "B1_P$B1") (pintype "bidirectional"))
    )
    (net (code "60") (name "Net-(U$11-P5)") (class "Default")
      (node (ref "U$11") (pin "P$6") (pinfunction "P5_P$6") (pintype "bidirectional"))
      (node (ref "U$14") (pin "P$6") (pinfunction "P5_P$6") (pintype "bidirectional"))
      (node (ref "U$14") (pin "P$7") (pinfunction "P6_P$7") (pintype "bidirectional"))
      (node (ref "U2") (pin "P$B2") (pinfunction "B2_P$B2") (pintype "bidirectional"))
    )
    (net (code "61") (name "Net-(U$12-P2)") (class "Default")
      (node (ref "U$12") (pin "P$3") (pinfunction "P2_P$3") (pintype "bidirectional"))
      (node (ref "U2") (pin "P$CLK") (pinfunction "CLK_P$CLK") (pintype "bidirectional"))
    )
    (net (code "62") (name "Net-(U$12-P3)") (class "Default")
      (node (ref "U$12") (pin "P$4") (pinfunction "P3_P$4") (pintype "bidirectional"))
      (node (ref "U2") (pin "P$RX") (pinfunction "RX_P$RX") (pintype "bidirectional"))
    )
    (net (code "63") (name "Net-(U$12-P4)") (class "Default")
      (node (ref "U$12") (pin "P$5") (pinfunction "P4_P$5") (pintype "bidirectional"))
      (node (ref "U2") (pin "P$TX") (pinfunction "TX_P$TX") (pintype "bidirectional"))
    )
    (net (code "64") (name "Net-(U$15-P2)") (class "Default")
      (node (ref "U$15") (pin "P$3") (pinfunction "P2_P$3") (pintype "bidirectional"))
      (node (ref "U$18") (pin "P$1") (pinfunction "P0_P$1") (pintype "bidirectional"))
      (node (ref "U3") (pin "P$A2") (pinfunction "A2_P$A2") (pintype "bidirectional"))
    )
    (net (code "65") (name "Net-(U$15-P3)") (class "Default")
      (node (ref "U$15") (pin "P$4") (pinfunction "P3_P$4") (pintype "bidirectional"))
      (node (ref "U$18") (pin "P$3") (pinfunction "P2_P$3") (pintype "bidirectional"))
      (node (ref "U3") (pin "P$A1") (pinfunction "A1_P$A1") (pintype "bidirectional"))
    )
    (net (code "66") (name "Net-(U$15-P4)") (class "Default")
      (node (ref "U$15") (pin "P$5") (pinfunction "P4_P$5") (pintype "bidirectional"))
      (node (ref "U$18") (pin "P$5") (pinfunction "P4_P$5") (pintype "bidirectional"))
      (node (ref "U3") (pin "P$B1") (pinfunction "B1_P$B1") (pintype "bidirectional"))
    )
    (net (code "67") (name "Net-(U$15-P5)") (class "Default")
      (node (ref "U$15") (pin "P$6") (pinfunction "P5_P$6") (pintype "bidirectional"))
      (node (ref "U$18") (pin "P$6") (pinfunction "P5_P$6") (pintype "bidirectional"))
      (node (ref "U$18") (pin "P$7") (pinfunction "P6_P$7") (pintype "bidirectional"))
      (node (ref "U3") (pin "P$B2") (pinfunction "B2_P$B2") (pintype "bidirectional"))
    )
    (net (code "68") (name "Net-(U$16-P2)") (class "Default")
      (node (ref "U$16") (pin "P$3") (pinfunction "P2_P$3") (pintype "bidirectional"))
      (node (ref "U3") (pin "P$CLK") (pinfunction "CLK_P$CLK") (pintype "bidirectional"))
    )
    (net (code "69") (name "Net-(U$16-P3)") (class "Default")
      (node (ref "U$16") (pin "P$4") (pinfunction "P3_P$4") (pintype "bidirectional"))
      (node (ref "U3") (pin "P$RX") (pinfunction "RX_P$RX") (pintype "bidirectional"))
    )
    (net (code "70") (name "Net-(U$16-P4)") (class "Default")
      (node (ref "U$16") (pin "P$5") (pinfunction "P4_P$5") (pintype "bidirectional"))
      (node (ref "U3") (pin "P$TX") (pinfunction "TX_P$TX") (pintype "bidirectional"))
    )
    (net (code "71") (name "Net-(U$23-P2)") (class "Default")
      (node (ref "U$23") (pin "P$3") (pinfunction "P2_P$3") (pintype "bidirectional"))
      (node (ref "U$26") (pin "P$1") (pinfunction "P0_P$1") (pintype "bidirectional"))
      (node (ref "U5") (pin "P$A2") (pinfunction "A2_P$A2") (pintype "bidirectional"))
    )
    (net (code "72") (name "Net-(U$23-P3)") (class "Default")
      (node (ref "U$23") (pin "P$4") (pinfunction "P3_P$4") (pintype "bidirectional"))
      (node (ref "U$26") (pin "P$3") (pinfunction "P2_P$3") (pintype "bidirectional"))
      (node (ref "U5") (pin "P$A1") (pinfunction "A1_P$A1") (pintype "bidirectional"))
    )
    (net (code "73") (name "Net-(U$23-P4)") (class "Default")
      (node (ref "U$23") (pin "P$5") (pinfunction "P4_P$5") (pintype "bidirectional"))
      (node (ref "U$26") (pin "P$5") (pinfunction "P4_P$5") (pintype "bidirectional"))
      (node (ref "U5") (pin "P$B1") (pinfunction "B1_P$B1") (pintype "bidirectional"))
    )
    (net (code "74") (name "Net-(U$23-P5)") (class "Default")
      (node (ref "U$23") (pin "P$6") (pinfunction "P5_P$6") (pintype "bidirectional"))
      (node (ref "U$26") (pin "P$6") (pinfunction "P5_P$6") (pintype "bidirectional"))
      (node (ref "U$26") (pin "P$7") (pinfunction "P6_P$7") (pintype "bidirectional"))
      (node (ref "U5") (pin "P$B2") (pinfunction "B2_P$B2") (pintype "bidirectional"))
    )
    (net (code "75") (name "Net-(U$24-P2)") (class "Default")
      (node (ref "U$24") (pin "P$3") (pinfunction "P2_P$3") (pintype "bidirectional"))
      (node (ref "U5") (pin "P$CLK") (pinfunction "CLK_P$CLK") (pintype "bidirectional"))
    )
    (net (code "76") (name "Net-(U$24-P3)") (class "Default")
      (node (ref "U$24") (pin "P$4") (pinfunction "P3_P$4") (pintype "bidirectional"))
      (node (ref "U5") (pin "P$RX") (pinfunction "RX_P$RX") (pintype "bidirectional"))
    )
    (net (code "77") (name "Net-(U$24-P4)") (class "Default")
      (node (ref "U$24") (pin "P$5") (pinfunction "P4_P$5") (pintype "bidirectional"))
      (node (ref "U5") (pin "P$TX") (pinfunction "TX_P$TX") (pintype "bidirectional"))
    )
    (net (code "78") (name "Net-(U$31-P2)") (class "Default")
      (node (ref "U$31") (pin "P$3") (pinfunction "P2_P$3") (pintype "bidirectional"))
      (node (ref "U$34") (pin "P$1") (pinfunction "P0_P$1") (pintype "bidirectional"))
      (node (ref "U4") (pin "P$A2") (pinfunction "A2_P$A2") (pintype "bidirectional"))
    )
    (net (code "79") (name "Net-(U$31-P3)") (class "Default")
      (node (ref "U$31") (pin "P$4") (pinfunction "P3_P$4") (pintype "bidirectional"))
      (node (ref "U$34") (pin "P$3") (pinfunction "P2_P$3") (pintype "bidirectional"))
      (node (ref "U4") (pin "P$A1") (pinfunction "A1_P$A1") (pintype "bidirectional"))
    )
    (net (code "80") (name "Net-(U$31-P4)") (class "Default")
      (node (ref "U$31") (pin "P$5") (pinfunction "P4_P$5") (pintype "bidirectional"))
      (node (ref "U$34") (pin "P$5") (pinfunction "P4_P$5") (pintype "bidirectional"))
      (node (ref "U4") (pin "P$B1") (pinfunction "B1_P$B1") (pintype "bidirectional"))
    )
    (net (code "81") (name "Net-(U$31-P5)") (class "Default")
      (node (ref "U$31") (pin "P$6") (pinfunction "P5_P$6") (pintype "bidirectional"))
      (node (ref "U$34") (pin "P$6") (pinfunction "P5_P$6") (pintype "bidirectional"))
      (node (ref "U$34") (pin "P$7") (pinfunction "P6_P$7") (pintype "bidirectional"))
      (node (ref "U4") (pin "P$B2") (pinfunction "B2_P$B2") (pintype "bidirectional"))
    )
    (net (code "82") (name "Net-(U$32-P2)") (class "Default")
      (node (ref "U$32") (pin "P$3") (pinfunction "P2_P$3") (pintype "bidirectional"))
      (node (ref "U4") (pin "P$CLK") (pinfunction "CLK_P$CLK") (pintype "bidirectional"))
    )
    (net (code "83") (name "Net-(U$32-P3)") (class "Default")
      (node (ref "U$32") (pin "P$4") (pinfunction "P3_P$4") (pintype "bidirectional"))
      (node (ref "U4") (pin "P$RX") (pinfunction "RX_P$RX") (pintype "bidirectional"))
    )
    (net (code "84") (name "Net-(U$32-P4)") (class "Default")
      (node (ref "U$32") (pin "P$5") (pinfunction "P4_P$5") (pintype "bidirectional"))
      (node (ref "U4") (pin "P$TX") (pinfunction "TX_P$TX") (pintype "bidirectional"))
    )
    (net (code "85") (name "Net-(U$39-P2)") (class "Default")
      (node (ref "U$39") (pin "P$3") (pinfunction "P2_P$3") (pintype "bidirectional"))
      (node (ref "U$42") (pin "P$1") (pinfunction "P0_P$1") (pintype "bidirectional"))
      (node (ref "U6") (pin "P$A2") (pinfunction "A2_P$A2") (pintype "bidirectional"))
    )
    (net (code "86") (name "Net-(U$39-P3)") (class "Default")
      (node (ref "U$39") (pin "P$4") (pinfunction "P3_P$4") (pintype "bidirectional"))
      (node (ref "U$42") (pin "P$3") (pinfunction "P2_P$3") (pintype "bidirectional"))
      (node (ref "U6") (pin "P$A1") (pinfunction "A1_P$A1") (pintype "bidirectional"))
    )
    (net (code "87") (name "Net-(U$39-P4)") (class "Default")
      (node (ref "U$39") (pin "P$5") (pinfunction "P4_P$5") (pintype "bidirectional"))
      (node (ref "U$42") (pin "P$5") (pinfunction "P4_P$5") (pintype "bidirectional"))
      (node (ref "U6") (pin "P$B1") (pinfunction "B1_P$B1") (pintype "bidirectional"))
    )
    (net (code "88") (name "Net-(U$39-P5)") (class "Default")
      (node (ref "U$39") (pin "P$6") (pinfunction "P5_P$6") (pintype "bidirectional"))
      (node (ref "U$42") (pin "P$6") (pinfunction "P5_P$6") (pintype "bidirectional"))
      (node (ref "U$42") (pin "P$7") (pinfunction "P6_P$7") (pintype "bidirectional"))
      (node (ref "U6") (pin "P$B2") (pinfunction "B2_P$B2") (pintype "bidirectional"))
    )
    (net (code "89") (name "Net-(U$40-P2)") (class "Default")
      (node (ref "U$40") (pin "P$3") (pinfunction "P2_P$3") (pintype "bidirectional"))
      (node (ref "U6") (pin "P$CLK") (pinfunction "CLK_P$CLK") (pintype "bidirectional"))
    )
    (net (code "90") (name "Net-(U$40-P3)") (class "Default")
      (node (ref "U$40") (pin "P$4") (pinfunction "P3_P$4") (pintype "bidirectional"))
      (node (ref "U6") (pin "P$RX") (pinfunction "RX_P$RX") (pintype "bidirectional"))
    )
    (net (code "91") (name "Net-(U$40-P4)") (class "Default")
      (node (ref "U$40") (pin "P$5") (pinfunction "P4_P$5") (pintype "bidirectional"))
      (node (ref "U6") (pin "P$TX") (pinfunction "TX_P$TX") (pintype "bidirectional"))
    )
    (net (code "92") (name "VIN") (class "Default")
      (node (ref "T_MCU") (pin "P1") (pinfunction "IN+_P1") (pintype "bidirectional"))
      (node (ref "U$11") (pin "P$1") (pinfunction "P0_P$1") (pintype "bidirectional"))
      (node (ref "U$15") (pin "P$1") (pinfunction "P0_P$1") (pintype "bidirectional"))
      (node (ref "U$23") (pin "P$1") (pinfunction "P0_P$1") (pintype "bidirectional"))
      (node (ref "U$3") (pin "P$1") (pinfunction "P0_P$1") (pintype "bidirectional"))
      (node (ref "U$31") (pin "P$1") (pinfunction "P0_P$1") (pintype "bidirectional"))
      (node (ref "U$39") (pin "P$1") (pinfunction "P0_P$1") (pintype "bidirectional"))
      (node (ref "U1") (pin "P$VM") (pinfunction "VM_P$VM") (pintype "bidirectional"))
      (node (ref "U2") (pin "P$VM") (pinfunction "VM_P$VM") (pintype "bidirectional"))
      (node (ref "U3") (pin "P$VM") (pinfunction "VM_P$VM") (pintype "bidirectional"))
      (node (ref "U4") (pin "P$VM") (pinfunction "VM_P$VM") (pintype "bidirectional"))
      (node (ref "U5") (pin "P$VM") (pinfunction "VM_P$VM") (pintype "bidirectional"))
      (node (ref "U6") (pin "P$VM") (pinfunction "VM_P$VM") (pintype "bidirectional"))
      (node (ref "X1") (pin "1") (pinfunction "KL_1") (pintype "passive"))
    )
    (net (code "93") (name "unconnected-(U$6-P1-PadP$2)") (class "Default")
      (node (ref "U$6") (pin "P$2") (pinfunction "P1_P$2") (pintype "bidirectional"))
    )
    (net (code "94") (name "unconnected-(U$6-P3-PadP$4)") (class "Default")
      (node (ref "U$6") (pin "P$4") (pinfunction "P3_P$4") (pintype "bidirectional"))
    )
    (net (code "95") (name "unconnected-(U$14-P1-PadP$2)") (class "Default")
      (node (ref "U$14") (pin "P$2") (pinfunction "P1_P$2") (pintype "bidirectional"))
    )
    (net (code "96") (name "unconnected-(U$14-P3-PadP$4)") (class "Default")
      (node (ref "U$14") (pin "P$4") (pinfunction "P3_P$4") (pintype "bidirectional"))
    )
    (net (code "97") (name "unconnected-(U$18-P1-PadP$2)") (class "Default")
      (node (ref "U$18") (pin "P$2") (pinfunction "P1_P$2") (pintype "bidirectional"))
    )
    (net (code "98") (name "unconnected-(U$18-P3-PadP$4)") (class "Default")
      (node (ref "U$18") (pin "P$4") (pinfunction "P3_P$4") (pintype "bidirectional"))
    )
    (net (code "99") (name "unconnected-(U$26-P1-PadP$2)") (class "Default")
      (node (ref "U$26") (pin "P$2") (pinfunction "P1_P$2") (pintype "bidirectional"))
    )
    (net (code "100") (name "unconnected-(U$26-P3-PadP$4)") (class "Default")
      (node (ref "U$26") (pin "P$4") (pinfunction "P3_P$4") (pintype "bidirectional"))
    )
    (net (code "101") (name "unconnected-(U$34-P1-PadP$2)") (class "Default")
      (node (ref "U$34") (pin "P$2") (pinfunction "P1_P$2") (pintype "bidirectional"))
    )
    (net (code "102") (name "unconnected-(U$34-P3-PadP$4)") (class "Default")
      (node (ref "U$34") (pin "P$4") (pinfunction "P3_P$4") (pintype "bidirectional"))
    )
    (net (code "103") (name "unconnected-(U$42-P1-PadP$2)") (class "Default")
      (node (ref "U$42") (pin "P$2") (pinfunction "P1_P$2") (pintype "bidirectional"))
    )
    (net (code "104") (name "unconnected-(U$42-P3-PadP$4)") (class "Default")
      (node (ref "U$42") (pin "P$4") (pinfunction "P3_P$4") (pintype "bidirectional"))
    )
  )
)
